# SCH_Joki_Fariz_2026-02-15.net
KiCad netlist of a schematic drawn in EasyEDA
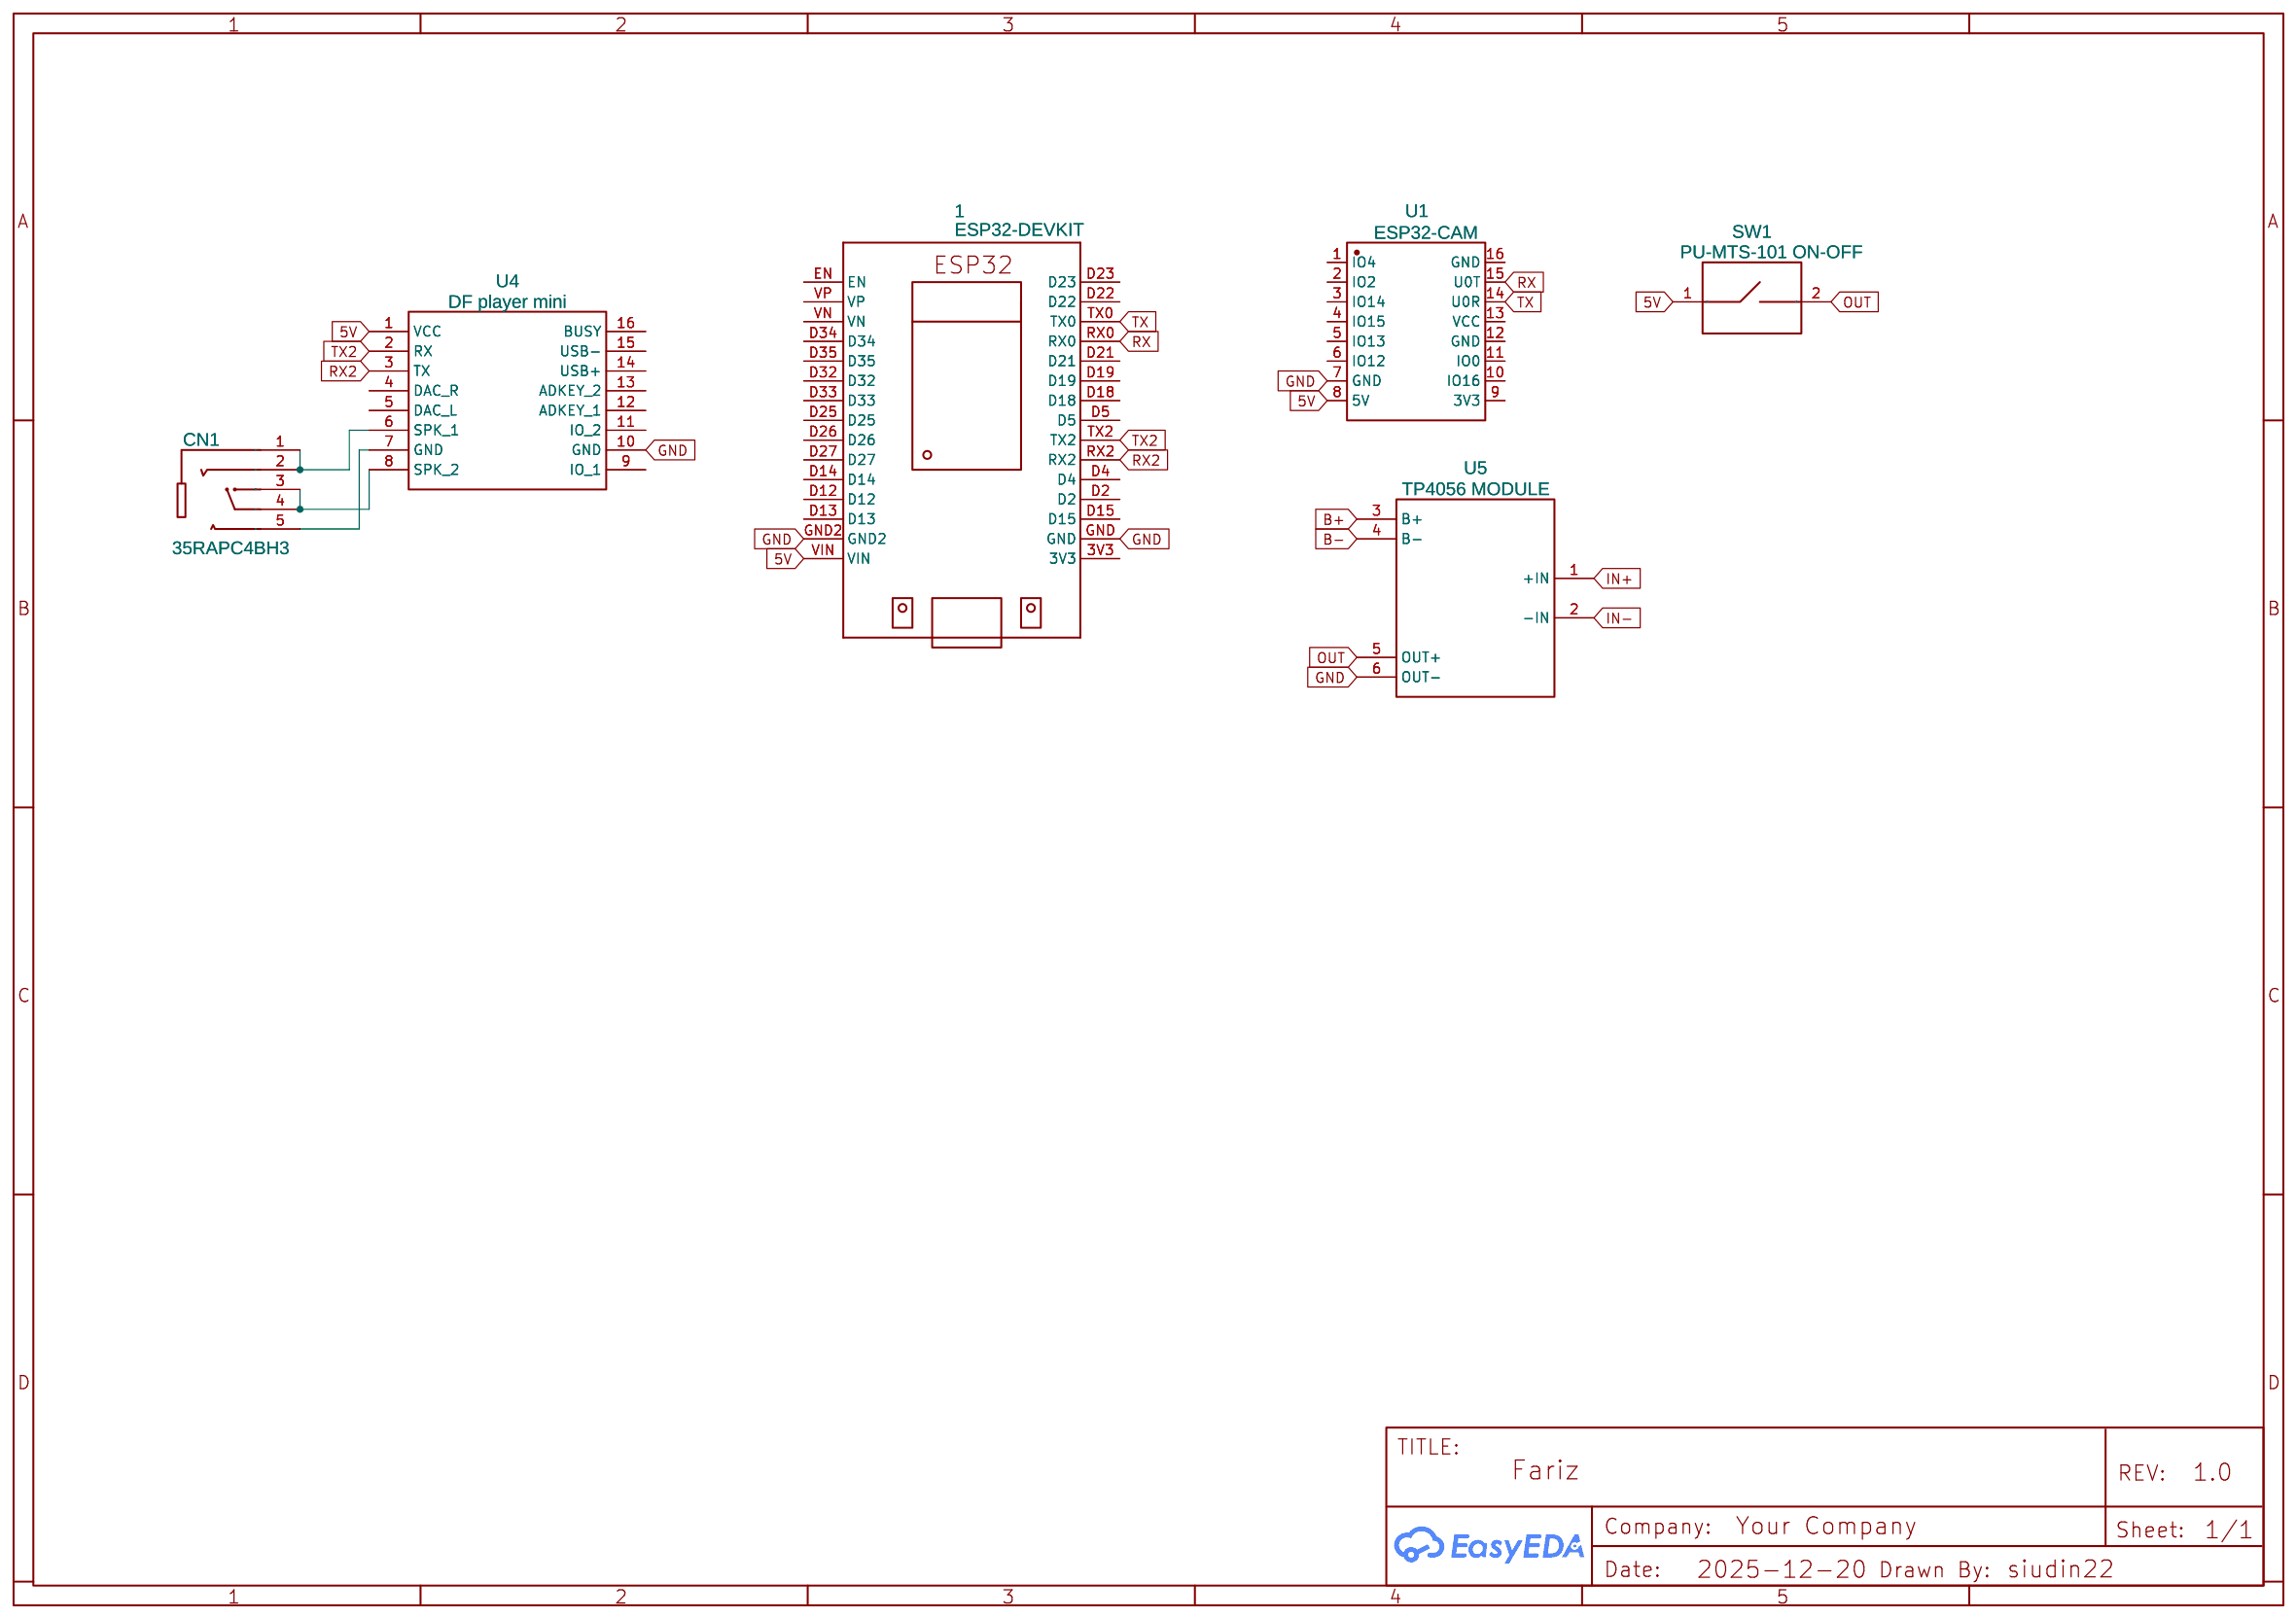
[diagram p0: schematic sheet]

(export (version "E")
  (design (tool "Eeschema 10.0.6"))
  (components
    (comp (ref "1") (value "ESP32-DEVKIT") (libsource (lib "") (part "ESP32-DEVKIT-V1-30PIN")))
    (comp (ref "CN1")
      (value "35RAPC4BH3")
      (fields (field (name "Manufacturer") "Switchcraft"))
      (libsource (lib "") (part "35RAPC4BH3"))
    )
    (comp (ref "SW1")
      (value "PU-MTS-101 ON-OFF")
      (fields (field (name "Manufacturer Part") "pu-mts-101 ON-OFF"))
      (libsource (lib "") (part "PU-MTS-101 ON-OFF"))
    )
    (comp (ref "U1")
      (value "ESP32-CAM")
      (fields (field (name "Manufacturer") "Ai-Thinker(安信可)"))
      (libsource (lib "") (part "ESP32-CAM"))
    )
    (comp (ref "U4") (value "DF player mini") (libsource (lib "") (part "DF player mini")))
    (comp (ref "U5") (value "TP4056 MODULE") (libsource (lib "") (part "TP4056 MODULE")))
  )
  (nets
    (net (code "1") (name "5V") (class "Default")
      (node (ref "1") (pin "VIN") (pinfunction "VIN_VIN") (pintype "unspecified"))
      (node (ref "SW1") (pin "1") (pinfunction "1_1") (pintype "unspecified"))
      (node (ref "U1") (pin "8") (pinfunction "5V_8") (pintype "unspecified"))
      (node (ref "U4") (pin "1") (pinfunction "VCC_1") (pintype "unspecified"))
    )
    (net (code "2") (name "B+") (class "Default")
      (node (ref "U5") (pin "3") (pinfunction "B+_3") (pintype "unspecified"))
    )
    (net (code "3") (name "B-") (class "Default")
      (node (ref "U5") (pin "4") (pinfunction "B-_4") (pintype "unspecified"))
    )
    (net (code "4") (name "GND") (class "Default")
      (node (ref "1") (pin "GND") (pinfunction "GND_GND") (pintype "unspecified"))
      (node (ref "1") (pin "GND2") (pinfunction "GND2_GND2") (pintype "unspecified"))
      (node (ref "U1") (pin "7") (pinfunction "GND_7") (pintype "unspecified"))
      (node (ref "U4") (pin "10") (pinfunction "GND_10") (pintype "unspecified"))
      (node (ref "U5") (pin "6") (pinfunction "OUT-_6") (pintype "unspecified"))
    )
    (net (code "5") (name "IN+") (class "Default")
      (node (ref "U5") (pin "1") (pinfunction "+IN_1") (pintype "unspecified"))
    )
    (net (code "6") (name "IN-") (class "Default")
      (node (ref "U5") (pin "2") (pinfunction "-IN_2") (pintype "unspecified"))
    )
    (net (code "7") (name "Net-(CN1-Pad5)") (class "Default")
      (node (ref "CN1") (pin "5") (pinfunction "5_5") (pintype "unspecified"))
      (node (ref "U4") (pin "7") (pinfunction "GND_7") (pintype "unspecified"))
    )
    (net (code "8") (name "Net-(U4-SPK_1)") (class "Default")
      (node (ref "CN1") (pin "1") (pinfunction "1_1") (pintype "unspecified"))
      (node (ref "CN1") (pin "2") (pinfunction "2_2") (pintype "unspecified"))
      (node (ref "U4") (pin "6") (pinfunction "SPK_1_6") (pintype "unspecified"))
    )
    (net (code "9") (name "Net-(U4-SPK_2)") (class "Default")
      (node (ref "CN1") (pin "3") (pinfunction "3_3") (pintype "unspecified"))
      (node (ref "CN1") (pin "4") (pinfunction "4_4") (pintype "unspecified"))
      (node (ref "U4") (pin "8") (pinfunction "SPK_2_8") (pintype "unspecified"))
    )
    (net (code "10") (name "OUT") (class "Default")
      (node (ref "SW1") (pin "2") (pinfunction "2_2") (pintype "unspecified"))
      (node (ref "U5") (pin "5") (pinfunction "OUT+_5") (pintype "unspecified"))
    )
    (net (code "11") (name "RX") (class "Default")
      (node (ref "1") (pin "RX0") (pinfunction "RX0_RX0") (pintype "unspecified"))
      (node (ref "U1") (pin "15") (pinfunction "U0T_15") (pintype "unspecified"))
    )
    (net (code "12") (name "RX2") (class "Default")
      (node (ref "1") (pin "RX2") (pinfunction "RX2_RX2") (pintype "unspecified"))
      (node (ref "U4") (pin "3") (pinfunction "TX_3") (pintype "unspecified"))
    )
    (net (code "13") (name "TX") (class "Default")
      (node (ref "1") (pin "TX0") (pinfunction "TX0_TX0") (pintype "unspecified"))
      (node (ref "U1") (pin "14") (pinfunction "U0R_14") (pintype "unspecified"))
    )
    (net (code "14") (name "TX2") (class "Default")
      (node (ref "1") (pin "TX2") (pinfunction "TX2_TX2") (pintype "unspecified"))
      (node (ref "U4") (pin "2") (pinfunction "RX_2") (pintype "unspecified"))
    )
    (net (code "15") (name "unconnected-(1-Pad3V3)") (class "Default")
      (node (ref "1") (pin "3V3") (pinfunction "3V3_3V3") (pintype "unspecified"))
    )
    (net (code "16") (name "unconnected-(1-PadD2)") (class "Default")
      (node (ref "1") (pin "D2") (pinfunction "D2_D2") (pintype "unspecified"))
    )
    (net (code "17") (name "unconnected-(1-PadD4)") (class "Default")
      (node (ref "1") (pin "D4") (pinfunction "D4_D4") (pintype "unspecified"))
    )
    (net (code "18") (name "unconnected-(1-PadD5)") (class "Default")
      (node (ref "1") (pin "D5") (pinfunction "D5_D5") (pintype "unspecified"))
    )
    (net (code "19") (name "unconnected-(1-PadD12)") (class "Default")
      (node (ref "1") (pin "D12") (pinfunction "D12_D12") (pintype "unspecified"))
    )
    (net (code "20") (name "unconnected-(1-PadD13)") (class "Default")
      (node (ref "1") (pin "D13") (pinfunction "D13_D13") (pintype "unspecified"))
    )
    (net (code "21") (name "unconnected-(1-PadD14)") (class "Default")
      (node (ref "1") (pin "D14") (pinfunction "D14_D14") (pintype "unspecified"))
    )
    (net (code "22") (name "unconnected-(1-PadD15)") (class "Default")
      (node (ref "1") (pin "D15") (pinfunction "D15_D15") (pintype "unspecified"))
    )
    (net (code "23") (name "unconnected-(1-PadD18)") (class "Default")
      (node (ref "1") (pin "D18") (pinfunction "D18_D18") (pintype "unspecified"))
    )
    (net (code "24") (name "unconnected-(1-PadD19)") (class "Default")
      (node (ref "1") (pin "D19") (pinfunction "D19_D19") (pintype "unspecified"))
    )
    (net (code "25") (name "unconnected-(1-PadD21)") (class "Default")
      (node (ref "1") (pin "D21") (pinfunction "D21_D21") (pintype "unspecified"))
    )
    (net (code "26") (name "unconnected-(1-PadD22)") (class "Default")
      (node (ref "1") (pin "D22") (pinfunction "D22_D22") (pintype "unspecified"))
    )
    (net (code "27") (name "unconnected-(1-PadD23)") (class "Default")
      (node (ref "1") (pin "D23") (pinfunction "D23_D23") (pintype "unspecified"))
    )
    (net (code "28") (name "unconnected-(1-PadD25)") (class "Default")
      (node (ref "1") (pin "D25") (pinfunction "D25_D25") (pintype "unspecified"))
    )
    (net (code "29") (name "unconnected-(1-PadD26)") (class "Default")
      (node (ref "1") (pin "D26") (pinfunction "D26_D26") (pintype "unspecified"))
    )
    (net (code "30") (name "unconnected-(1-PadD27)") (class "Default")
      (node (ref "1") (pin "D27") (pinfunction "D27_D27") (pintype "unspecified"))
    )
    (net (code "31") (name "unconnected-(1-PadD32)") (class "Default")
      (node (ref "1") (pin "D32") (pinfunction "D32_D32") (pintype "unspecified"))
    )
    (net (code "32") (name "unconnected-(1-PadD33)") (class "Default")
      (node (ref "1") (pin "D33") (pinfunction "D33_D33") (pintype "unspecified"))
    )
    (net (code "33") (name "unconnected-(1-PadD34)") (class "Default")
      (node (ref "1") (pin "D34") (pinfunction "D34_D34") (pintype "unspecified"))
    )
    (net (code "34") (name "unconnected-(1-PadD35)") (class "Default")
      (node (ref "1") (pin "D35") (pinfunction "D35_D35") (pintype "unspecified"))
    )
    (net (code "35") (name "unconnected-(1-PadEN)") (class "Default")
      (node (ref "1") (pin "EN") (pinfunction "EN_EN") (pintype "unspecified"))
    )
    (net (code "36") (name "unconnected-(1-PadVN)") (class "Default")
      (node (ref "1") (pin "VN") (pinfunction "VN_VN") (pintype "unspecified"))
    )
    (net (code "37") (name "unconnected-(1-PadVP)") (class "Default")
      (node (ref "1") (pin "VP") (pinfunction "VP_VP") (pintype "unspecified"))
    )
    (net (code "38") (name "unconnected-(U1-3V3-Pad9)") (class "Default")
      (node (ref "U1") (pin "9") (pinfunction "3V3_9") (pintype "unspecified"))
    )
    (net (code "39") (name "unconnected-(U1-GND-Pad12)") (class "Default")
      (node (ref "U1") (pin "12") (pinfunction "GND_12") (pintype "unspecified"))
    )
    (net (code "40") (name "unconnected-(U1-GND-Pad16)") (class "Default")
      (node (ref "U1") (pin "16") (pinfunction "GND_16") (pintype "unspecified"))
    )
    (net (code "41") (name "unconnected-(U1-IO0-Pad11)") (class "Default")
      (node (ref "U1") (pin "11") (pinfunction "IO0_11") (pintype "unspecified"))
    )
    (net (code "42") (name "unconnected-(U1-IO2-Pad2)") (class "Default")
      (node (ref "U1") (pin "2") (pinfunction "IO2_2") (pintype "unspecified"))
    )
    (net (code "43") (name "unconnected-(U1-IO4-Pad1)") (class "Default")
      (node (ref "U1") (pin "1") (pinfunction "IO4_1") (pintype "unspecified"))
    )
    (net (code "44") (name "unconnected-(U1-IO12-Pad6)") (class "Default")
      (node (ref "U1") (pin "6") (pinfunction "IO12_6") (pintype "unspecified"))
    )
    (net (code "45") (name "unconnected-(U1-IO13-Pad5)") (class "Default")
      (node (ref "U1") (pin "5") (pinfunction "IO13_5") (pintype "unspecified"))
    )
    (net (code "46") (name "unconnected-(U1-IO14-Pad3)") (class "Default")
      (node (ref "U1") (pin "3") (pinfunction "IO14_3") (pintype "unspecified"))
    )
    (net (code "47") (name "unconnected-(U1-IO15-Pad4)") (class "Default")
      (node (ref "U1") (pin "4") (pinfunction "IO15_4") (pintype "unspecified"))
    )
    (net (code "48") (name "unconnected-(U1-IO16-Pad10)") (class "Default")
      (node (ref "U1") (pin "10") (pinfunction "IO16_10") (pintype "unspecified"))
    )
    (net (code "49") (name "unconnected-(U1-VCC-Pad13)") (class "Default")
      (node (ref "U1") (pin "13") (pinfunction "VCC_13") (pintype "unspecified"))
    )
    (net (code "50") (name "unconnected-(U4-ADKEY_1-Pad12)") (class "Default")
      (node (ref "U4") (pin "12") (pinfunction "ADKEY_1_12") (pintype "unspecified"))
    )
    (net (code "51") (name "unconnected-(U4-ADKEY_2-Pad13)") (class "Default")
      (node (ref "U4") (pin "13") (pinfunction "ADKEY_2_13") (pintype "unspecified"))
    )
    (net (code "52") (name "unconnected-(U4-BUSY-Pad16)") (class "Default")
      (node (ref "U4") (pin "16") (pinfunction "BUSY_16") (pintype "unspecified"))
    )
    (net (code "53") (name "unconnected-(U4-DAC_L-Pad5)") (class "Default")
      (node (ref "U4") (pin "5") (pinfunction "DAC_L_5") (pintype "unspecified"))
    )
    (net (code "54") (name "unconnected-(U4-DAC_R-Pad4)") (class "Default")
      (node (ref "U4") (pin "4") (pinfunction "DAC_R_4") (pintype "unspecified"))
    )
    (net (code "55") (name "unconnected-(U4-IO_1-Pad9)") (class "Default")
      (node (ref "U4") (pin "9") (pinfunction "IO_1_9") (pintype "unspecified"))
    )
    (net (code "56") (name "unconnected-(U4-IO_2-Pad11)") (class "Default")
      (node (ref "U4") (pin "11") (pinfunction "IO_2_11") (pintype "unspecified"))
    )
    (net (code "57") (name "unconnected-(U4-USB+-Pad14)") (class "Default")
      (node (ref "U4") (pin "14") (pinfunction "USB+_14") (pintype "unspecified"))
    )
    (net (code "58") (name "unconnected-(U4-USB--Pad15)") (class "Default")
      (node (ref "U4") (pin "15") (pinfunction "USB-_15") (pintype "unspecified"))
    )
  )
)
